# lixie_schematic.net
KiCad netlist of a schematic drawn in Altium Designer
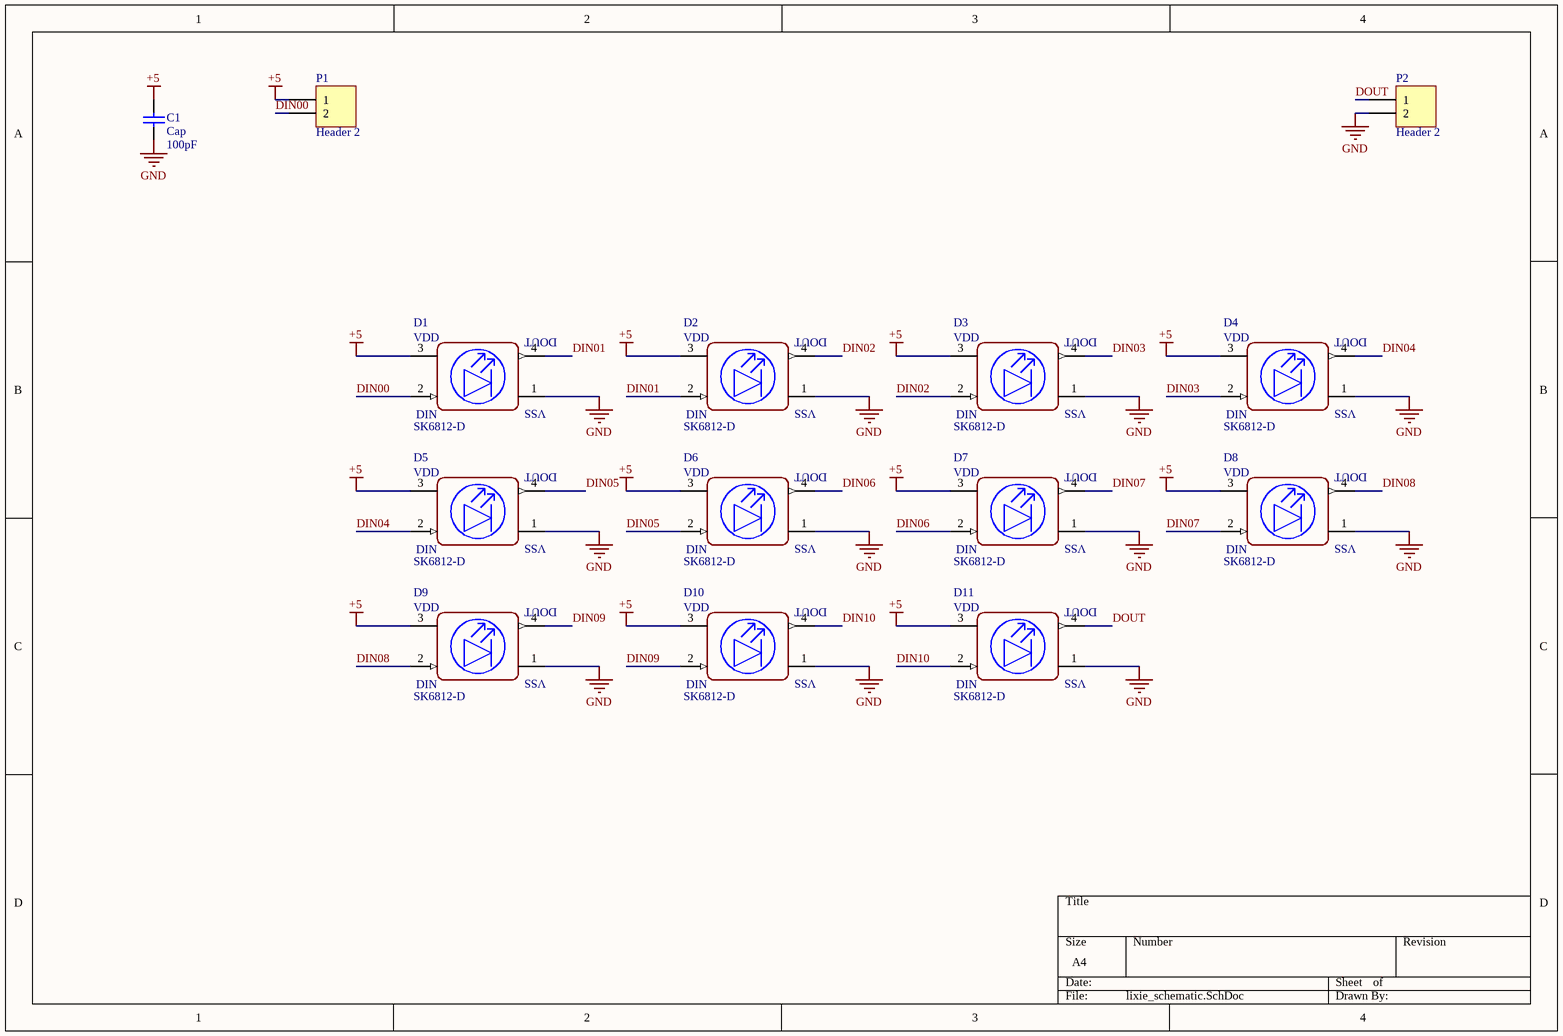
[diagram p0: lixie_schematic.SchDoc]

(export (version "E")
  (design (tool "Eeschema 10.0.6"))
  (components
    (comp (ref "C1")
      (value "Cap")
      (footprint "RAD-0.3")
      (description "Capacitor")
      (fields (field (name "ALTIUM_VALUE") "100pF") (field (name "PUBLISHER") "Altium Limited"))
      (libsource (lib "Miscellaneous Devices") (part "Cap"))
    )
    (comp (ref "D1")
      (value "Diode_Adafruit_SK6812-D_eec")
      (footprint "Adafruit_SK6812-D_0")
      (fields (field (name "PART NUMBER") "SK6812-D") (field (name "MANUFACTURER") "Adafruit"))
      (libsource (lib "Diode_Adafruit_SK6812-D_eec") (part "Diode_Adafruit_SK6812-D_eec"))
    )
    (comp (ref "D2")
      (value "Diode_Adafruit_SK6812-D_eec")
      (footprint "Adafruit_SK6812-D_0")
      (fields (field (name "PART NUMBER") "SK6812-D") (field (name "MANUFACTURER") "Adafruit"))
      (libsource (lib "Diode_Adafruit_SK6812-D_eec") (part "Diode_Adafruit_SK6812-D_eec"))
    )
    (comp (ref "D3")
      (value "~")
      (footprint "Adafruit_SK6812-D_0")
      (fields (field (name "PART NUMBER") "SK6812-D") (field (name "MANUFACTURER") "Adafruit"))
      (libsource (lib "Diode_Adafruit_SK6812-D_eec") (part "Diode_Adafruit_SK6812-D_eec"))
    )
    (comp (ref "D4")
      (value "Diode_Adafruit_SK6812-D_eec")
      (footprint "Adafruit_SK6812-D_0")
      (fields (field (name "PART NUMBER") "SK6812-D") (field (name "MANUFACTURER") "Adafruit"))
      (libsource (lib "Diode_Adafruit_SK6812-D_eec") (part "Diode_Adafruit_SK6812-D_eec"))
    )
    (comp (ref "D5")
      (value "Diode_Adafruit_SK6812-D_eec")
      (footprint "Adafruit_SK6812-D_0")
      (fields (field (name "PART NUMBER") "SK6812-D") (field (name "MANUFACTURER") "Adafruit"))
      (libsource (lib "Diode_Adafruit_SK6812-D_eec") (part "Diode_Adafruit_SK6812-D_eec"))
    )
    (comp (ref "D6")
      (value "Diode_Adafruit_SK6812-D_eec")
      (footprint "Adafruit_SK6812-D_0")
      (fields (field (name "PART NUMBER") "SK6812-D") (field (name "MANUFACTURER") "Adafruit"))
      (libsource (lib "Diode_Adafruit_SK6812-D_eec") (part "Diode_Adafruit_SK6812-D_eec"))
    )
    (comp (ref "D7")
      (value "Diode_Adafruit_SK6812-D_eec")
      (footprint "Adafruit_SK6812-D_0")
      (fields (field (name "PART NUMBER") "SK6812-D") (field (name "MANUFACTURER") "Adafruit"))
      (libsource (lib "Diode_Adafruit_SK6812-D_eec") (part "Diode_Adafruit_SK6812-D_eec"))
    )
    (comp (ref "D8")
      (value "Diode_Adafruit_SK6812-D_eec")
      (footprint "Adafruit_SK6812-D_0")
      (fields (field (name "PART NUMBER") "SK6812-D") (field (name "MANUFACTURER") "Adafruit"))
      (libsource (lib "Diode_Adafruit_SK6812-D_eec") (part "Diode_Adafruit_SK6812-D_eec"))
    )
    (comp (ref "D9")
      (value "Diode_Adafruit_SK6812-D_eec")
      (footprint "Adafruit_SK6812-D_0")
      (fields (field (name "PART NUMBER") "SK6812-D") (field (name "MANUFACTURER") "Adafruit"))
      (libsource (lib "Diode_Adafruit_SK6812-D_eec") (part "Diode_Adafruit_SK6812-D_eec"))
    )
    (comp (ref "D10")
      (value "Diode_Adafruit_SK6812-D_eec")
      (footprint "Adafruit_SK6812-D_0")
      (fields (field (name "PART NUMBER") "SK6812-D") (field (name "MANUFACTURER") "Adafruit"))
      (libsource (lib "Diode_Adafruit_SK6812-D_eec") (part "Diode_Adafruit_SK6812-D_eec"))
    )
    (comp (ref "D11")
      (value "Diode_Adafruit_SK6812-D_eec")
      (footprint "Adafruit_SK6812-D_0")
      (fields (field (name "PART NUMBER") "SK6812-D") (field (name "MANUFACTURER") "Adafruit"))
      (libsource (lib "Diode_Adafruit_SK6812-D_eec") (part "Diode_Adafruit_SK6812-D_eec"))
    )
    (comp (ref "P1")
      (value "Header 2")
      (footprint "HDR1X2")
      (description "Header, 2-Pin")
      (fields (field (name "PUBLISHER") "Altium Limited"))
      (libsource (lib "Miscellaneous Connectors") (part "Header 2"))
    )
    (comp (ref "P2")
      (value "Header 2")
      (footprint "HDR1X2")
      (description "Header, 2-Pin")
      (fields (field (name "PUBLISHER") "Altium Limited"))
      (libsource (lib "Miscellaneous Connectors") (part "Header 2"))
    )
  )
  (nets
    (net (code "1") (name "+5") (class "Default")
      (node (ref "C1") (pin "2") (pinfunction "2_2") (pintype "passive"))
      (node (ref "D1") (pin "3") (pinfunction "VDD_3") (pintype "power_in"))
      (node (ref "D10") (pin "3") (pinfunction "VDD_3") (pintype "power_in"))
      (node (ref "D11") (pin "3") (pinfunction "VDD_3") (pintype "power_in"))
      (node (ref "D2") (pin "3") (pinfunction "VDD_3") (pintype "power_in"))
      (node (ref "D3") (pin "3") (pinfunction "VDD_3") (pintype "power_in"))
      (node (ref "D4") (pin "3") (pinfunction "VDD_3") (pintype "power_in"))
      (node (ref "D5") (pin "3") (pinfunction "VDD_3") (pintype "power_in"))
      (node (ref "D6") (pin "3") (pinfunction "VDD_3") (pintype "power_in"))
      (node (ref "D7") (pin "3") (pinfunction "VDD_3") (pintype "power_in"))
      (node (ref "D8") (pin "3") (pinfunction "VDD_3") (pintype "power_in"))
      (node (ref "D9") (pin "3") (pinfunction "VDD_3") (pintype "power_in"))
      (node (ref "P1") (pin "1") (pinfunction "1_1") (pintype "passive"))
    )
    (net (code "2") (name "/DIN00") (class "Default")
      (node (ref "D1") (pin "2") (pinfunction "DIN_2") (pintype "input"))
      (node (ref "P1") (pin "2") (pinfunction "2_2") (pintype "passive"))
    )
    (net (code "3") (name "/DIN01") (class "Default")
      (node (ref "D1") (pin "4") (pinfunction "DOUT_4") (pintype "output"))
      (node (ref "D2") (pin "2") (pinfunction "DIN_2") (pintype "input"))
    )
    (net (code "4") (name "/DIN02") (class "Default")
      (node (ref "D2") (pin "4") (pinfunction "DOUT_4") (pintype "output"))
      (node (ref "D3") (pin "2") (pinfunction "DIN_2") (pintype "input"))
    )
    (net (code "5") (name "/DIN03") (class "Default")
      (node (ref "D3") (pin "4") (pinfunction "DOUT_4") (pintype "output"))
      (node (ref "D4") (pin "2") (pinfunction "DIN_2") (pintype "input"))
    )
    (net (code "6") (name "/DIN04") (class "Default")
      (node (ref "D4") (pin "4") (pinfunction "DOUT_4") (pintype "output"))
      (node (ref "D5") (pin "2") (pinfunction "DIN_2") (pintype "input"))
    )
    (net (code "7") (name "/DIN05") (class "Default")
      (node (ref "D5") (pin "4") (pinfunction "DOUT_4") (pintype "output"))
      (node (ref "D6") (pin "2") (pinfunction "DIN_2") (pintype "input"))
    )
    (net (code "8") (name "/DIN06") (class "Default")
      (node (ref "D6") (pin "4") (pinfunction "DOUT_4") (pintype "output"))
      (node (ref "D7") (pin "2") (pinfunction "DIN_2") (pintype "input"))
    )
    (net (code "9") (name "/DIN07") (class "Default")
      (node (ref "D7") (pin "4") (pinfunction "DOUT_4") (pintype "output"))
      (node (ref "D8") (pin "2") (pinfunction "DIN_2") (pintype "input"))
    )
    (net (code "10") (name "/DIN08") (class "Default")
      (node (ref "D8") (pin "4") (pinfunction "DOUT_4") (pintype "output"))
      (node (ref "D9") (pin "2") (pinfunction "DIN_2") (pintype "input"))
    )
    (net (code "11") (name "/DIN09") (class "Default")
      (node (ref "D10") (pin "2") (pinfunction "DIN_2") (pintype "input"))
      (node (ref "D9") (pin "4") (pinfunction "DOUT_4") (pintype "output"))
    )
    (net (code "12") (name "/DIN10") (class "Default")
      (node (ref "D10") (pin "4") (pinfunction "DOUT_4") (pintype "output"))
      (node (ref "D11") (pin "2") (pinfunction "DIN_2") (pintype "input"))
    )
    (net (code "13") (name "/DOUT") (class "Default")
      (node (ref "D11") (pin "4") (pinfunction "DOUT_4") (pintype "output"))
      (node (ref "P2") (pin "1") (pinfunction "1_1") (pintype "passive"))
    )
    (net (code "14") (name "GND") (class "Default")
      (node (ref "C1") (pin "1") (pinfunction "1_1") (pintype "passive"))
      (node (ref "D1") (pin "1") (pinfunction "VSS_1") (pintype "power_in"))
      (node (ref "D10") (pin "1") (pinfunction "VSS_1") (pintype "power_in"))
      (node (ref "D11") (pin "1") (pinfunction "VSS_1") (pintype "power_in"))
      (node (ref "D2") (pin "1") (pinfunction "VSS_1") (pintype "power_in"))
      (node (ref "D3") (pin "1") (pinfunction "VSS_1") (pintype "power_in"))
      (node (ref "D4") (pin "1") (pinfunction "VSS_1") (pintype "power_in"))
      (node (ref "D5") (pin "1") (pinfunction "VSS_1") (pintype "power_in"))
      (node (ref "D6") (pin "1") (pinfunction "VSS_1") (pintype "power_in"))
      (node (ref "D7") (pin "1") (pinfunction "VSS_1") (pintype "power_in"))
      (node (ref "D8") (pin "1") (pinfunction "VSS_1") (pintype "power_in"))
      (node (ref "D9") (pin "1") (pinfunction "VSS_1") (pintype "power_in"))
      (node (ref "P2") (pin "2") (pinfunction "2_2") (pintype "passive"))
    )
  )
)
